# NBMC_SCHEMATIC_wout_thermistor_bridge_ex.net
KiCad netlist of a schematic drawn in EAGLE
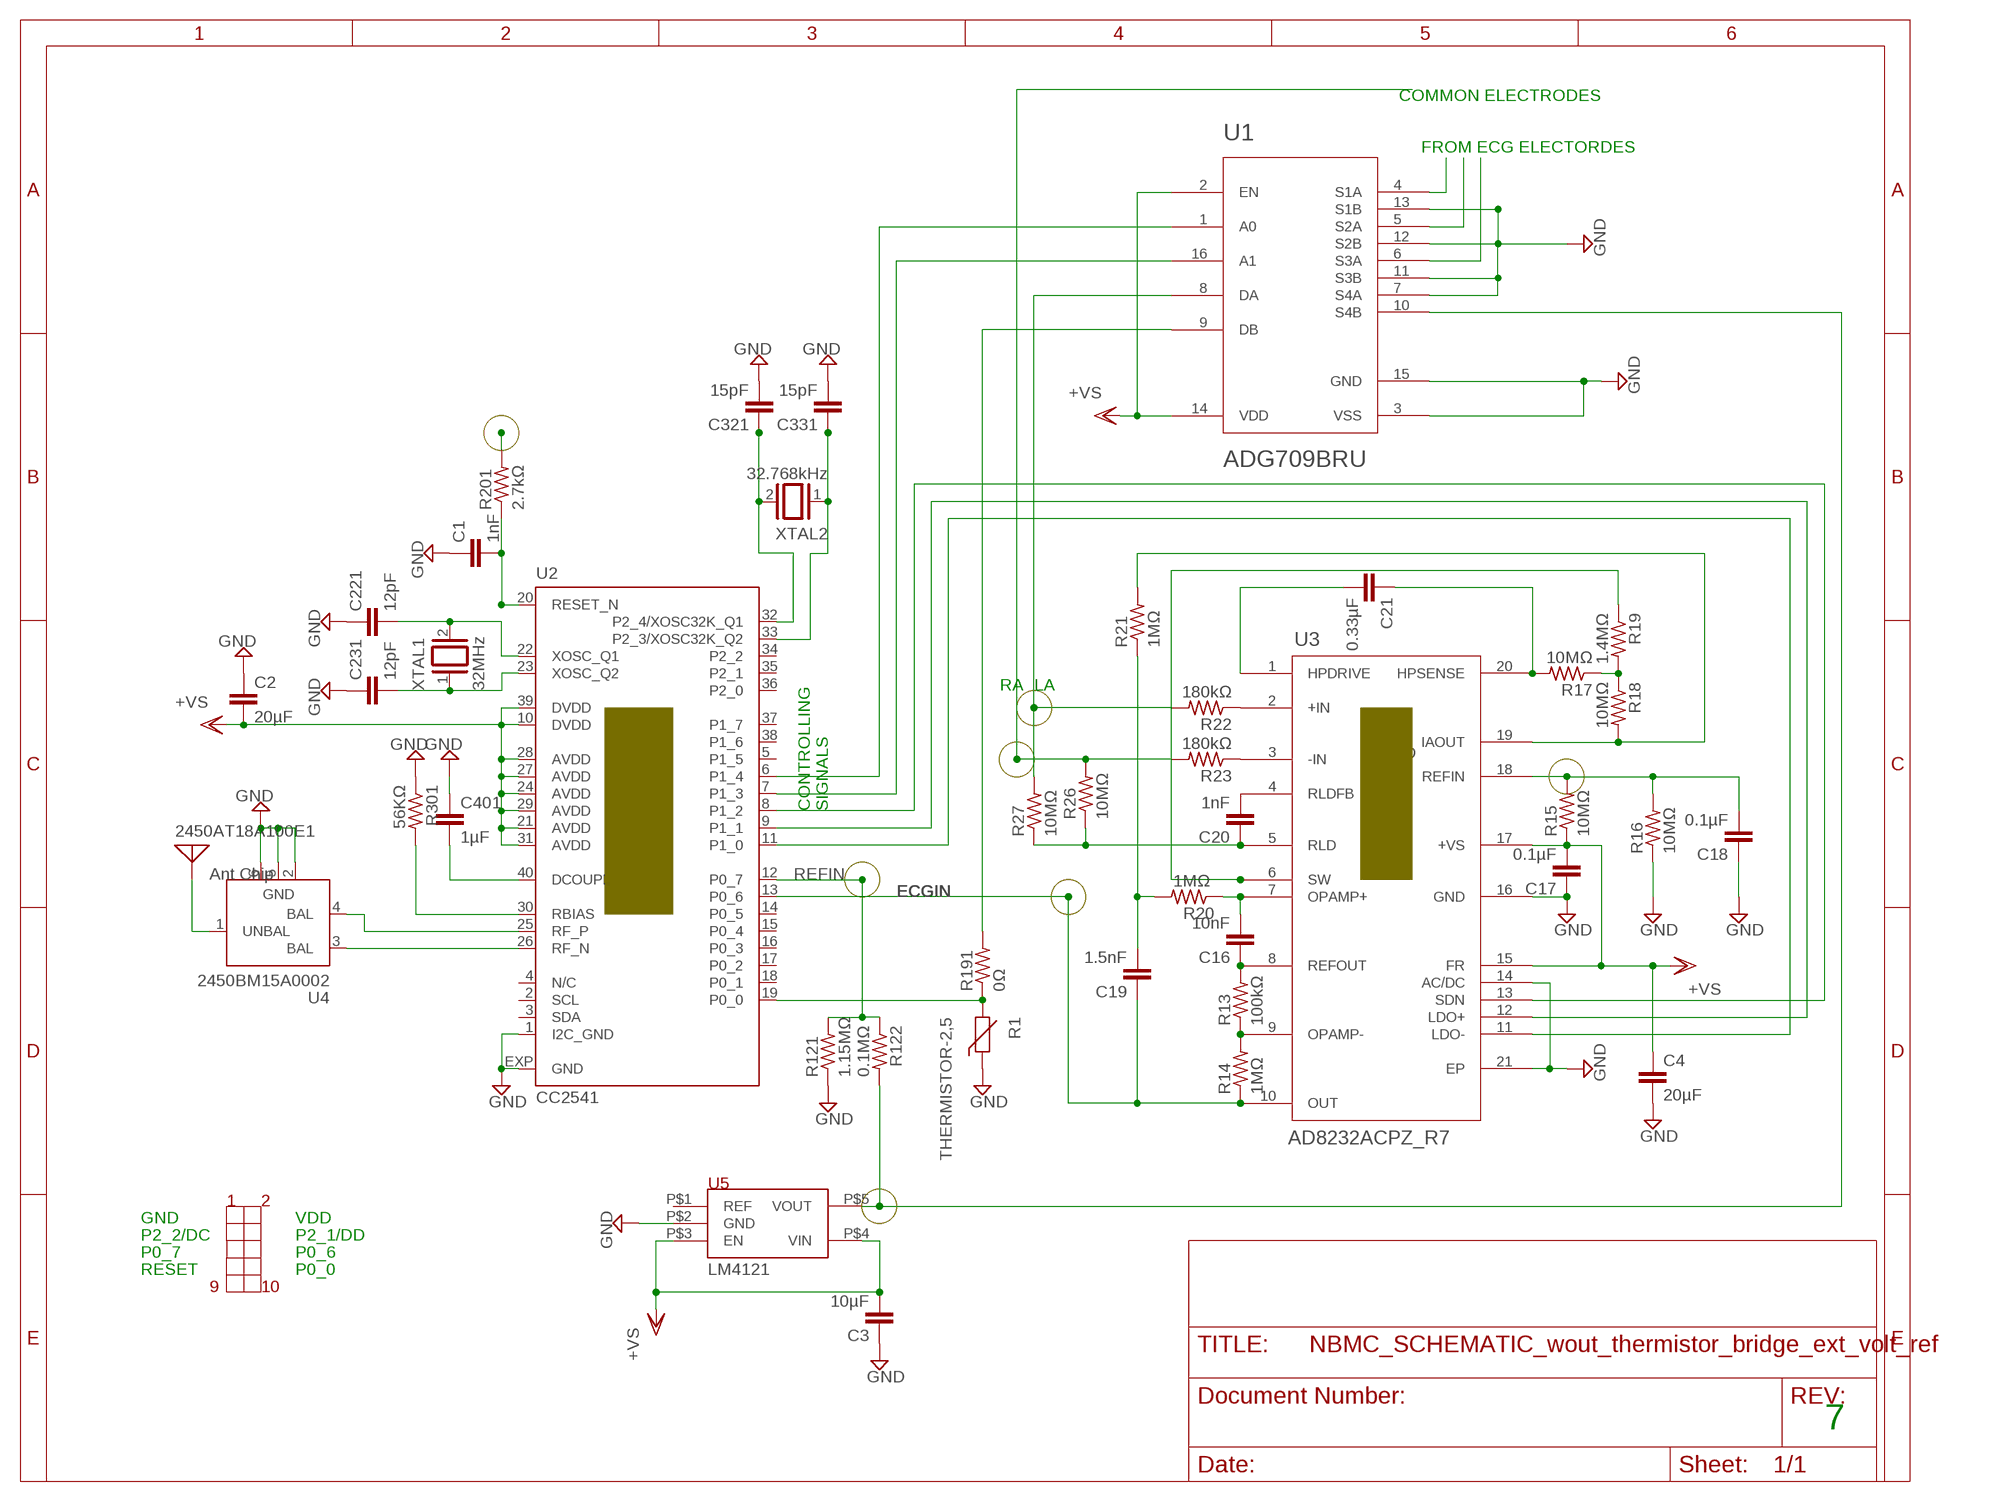
[diagram p0: schematic, sheet 1]

(export (version "E")
  (design (tool "Eeschema 10.0.6"))
  (components
    (comp (ref "2450AT18A100E1")
      (value "Ant Chip")
      (footprint "eagle-import:PAD-01")
      (libsource (lib "eagle-import") (part "ANTENNA"))
    )
    (comp (ref "C1")
      (value "1nF")
      (footprint "eagle-import:C0402")
      (libsource (lib "eagle-import") (part "C-EUC0402"))
    )
    (comp (ref "C2")
      (value "20µF")
      (footprint "eagle-import:C0402")
      (libsource (lib "eagle-import") (part "C-EUC0402"))
    )
    (comp (ref "C3")
      (value "10µF")
      (footprint "eagle-import:C0402")
      (libsource (lib "eagle-import") (part "C-EUC0402"))
    )
    (comp (ref "C4")
      (value "20µF")
      (footprint "eagle-import:C0402")
      (libsource (lib "eagle-import") (part "C-EUC0402"))
    )
    (comp (ref "C16")
      (value "10nF")
      (footprint "eagle-import:C0402")
      (libsource (lib "eagle-import") (part "C-EUC0402"))
    )
    (comp (ref "C17")
      (value "0.1µF")
      (footprint "eagle-import:C0402")
      (libsource (lib "eagle-import") (part "C-EUC0402"))
    )
    (comp (ref "C18")
      (value "0.1µF")
      (footprint "eagle-import:C0402")
      (libsource (lib "eagle-import") (part "C-EUC0402"))
    )
    (comp (ref "C19")
      (value "1.5nF")
      (footprint "eagle-import:C0402")
      (libsource (lib "eagle-import") (part "C-EUC0402"))
    )
    (comp (ref "C20")
      (value "1nF")
      (footprint "eagle-import:C0402")
      (libsource (lib "eagle-import") (part "C-EUC0402"))
    )
    (comp (ref "C21")
      (value "0.33µF")
      (footprint "eagle-import:C0402")
      (libsource (lib "eagle-import") (part "C-EUC0402"))
    )
    (comp (ref "C221")
      (value "12pF")
      (footprint "eagle-import:C0402")
      (libsource (lib "eagle-import") (part "C-EUC0402"))
    )
    (comp (ref "C231")
      (value "12pF")
      (footprint "eagle-import:C0402")
      (libsource (lib "eagle-import") (part "C-EUC0402"))
    )
    (comp (ref "C321")
      (value "15pF")
      (footprint "eagle-import:C0402")
      (libsource (lib "eagle-import") (part "C-EUC0402"))
    )
    (comp (ref "C331")
      (value "15pF")
      (footprint "eagle-import:C0402")
      (libsource (lib "eagle-import") (part "C-EUC0402"))
    )
    (comp (ref "C401")
      (value "1µF")
      (footprint "eagle-import:C0402")
      (libsource (lib "eagle-import") (part "C-EUC0402"))
    )
    (comp (ref "R1")
      (value "THERMISTOR-2,5")
      (footprint "eagle-import:RS-2,5")
      (libsource (lib "eagle-import") (part "THERMISTOR-2,5"))
    )
    (comp (ref "R13")
      (value "100kΩ")
      (footprint "eagle-import:R0402")
      (libsource (lib "eagle-import") (part "R-US_R0402"))
    )
    (comp (ref "R14")
      (value "1MΩ")
      (footprint "eagle-import:R0402")
      (libsource (lib "eagle-import") (part "R-US_R0402"))
    )
    (comp (ref "R15")
      (value "10MΩ")
      (footprint "eagle-import:R0402")
      (libsource (lib "eagle-import") (part "R-US_R0402"))
    )
    (comp (ref "R16")
      (value "10MΩ")
      (footprint "eagle-import:R0402")
      (libsource (lib "eagle-import") (part "R-US_R0402"))
    )
    (comp (ref "R17")
      (value "10MΩ")
      (footprint "eagle-import:R0402")
      (libsource (lib "eagle-import") (part "R-US_R0402"))
    )
    (comp (ref "R18")
      (value "10MΩ")
      (footprint "eagle-import:R0402")
      (libsource (lib "eagle-import") (part "R-US_R0402"))
    )
    (comp (ref "R19")
      (value "1.4MΩ")
      (footprint "eagle-import:R0402")
      (libsource (lib "eagle-import") (part "R-US_R0402"))
    )
    (comp (ref "R20")
      (value "1MΩ")
      (footprint "eagle-import:R0402")
      (libsource (lib "eagle-import") (part "R-US_R0402"))
    )
    (comp (ref "R21")
      (value "1MΩ")
      (footprint "eagle-import:R0402")
      (libsource (lib "eagle-import") (part "R-US_R0402"))
    )
    (comp (ref "R22")
      (value "180kΩ")
      (footprint "eagle-import:R0402")
      (libsource (lib "eagle-import") (part "R-US_R0402"))
    )
    (comp (ref "R23")
      (value "180kΩ")
      (footprint "eagle-import:R0402")
      (libsource (lib "eagle-import") (part "R-US_R0402"))
    )
    (comp (ref "R26")
      (value "10MΩ")
      (footprint "eagle-import:R0402")
      (libsource (lib "eagle-import") (part "R-US_R0402"))
    )
    (comp (ref "R27")
      (value "10MΩ")
      (footprint "eagle-import:R0402")
      (libsource (lib "eagle-import") (part "R-US_R0402"))
    )
    (comp (ref "R121")
      (value "1.15MΩ")
      (footprint "eagle-import:R0402")
      (libsource (lib "eagle-import") (part "R-US_R0402"))
    )
    (comp (ref "R122")
      (value "0.1MΩ")
      (footprint "eagle-import:R0402")
      (libsource (lib "eagle-import") (part "R-US_R0402"))
    )
    (comp (ref "R191")
      (value "0Ω")
      (footprint "eagle-import:R0402")
      (libsource (lib "eagle-import") (part "R-US_R0402"))
    )
    (comp (ref "R201")
      (value "2.7kΩ")
      (footprint "eagle-import:R0402")
      (libsource (lib "eagle-import") (part "R-US_R0402"))
    )
    (comp (ref "R301")
      (value "56KΩ")
      (footprint "eagle-import:R0402")
      (libsource (lib "eagle-import") (part "R-US_R0402"))
    )
    (comp (ref "U1")
      (value "ADG709BRU")
      (footprint "eagle-import:RU_16")
      (libsource (lib "eagle-import") (part "ADG709BRU"))
    )
    (comp (ref "U2")
      (value "CC2541")
      (footprint "eagle-import:RHA_S-PVQFN-N40")
      (libsource (lib "eagle-import") (part "CC2541"))
    )
    (comp (ref "U3")
      (value "AD8232ACPZ_R7")
      (footprint "eagle-import:CP_20_10")
      (libsource (lib "eagle-import") (part "AD8232ACPZ_R7"))
    )
    (comp (ref "U4")
      (value "2450BM15A0002")
      (footprint "eagle-import:2450BM15A0002")
      (libsource (lib "eagle-import") (part "2450BM15A0002"))
    )
    (comp (ref "U5")
      (value "LM4121")
      (footprint "eagle-import:0402")
      (libsource (lib "eagle-import") (part "LM4121"))
    )
    (comp (ref "XTAL1")
      (value "32MHz")
      (footprint "eagle-import:Q")
      (libsource (lib "eagle-import") (part "XTAL"))
    )
    (comp (ref "XTAL2")
      (value "32.768kHz")
      (footprint "eagle-import:Q")
      (libsource (lib "eagle-import") (part "XTAL"))
    )
  )
  (nets
    (net (code "1") (name "+VS") (class "Default")
      (node (ref "C17") (pin "2") (pinfunction "2_2") (pintype "passive"))
      (node (ref "C2") (pin "2") (pinfunction "2_2") (pintype "passive"))
      (node (ref "C3") (pin "2") (pinfunction "2_2") (pintype "passive"))
      (node (ref "C4") (pin "1") (pinfunction "1_1") (pintype "passive"))
      (node (ref "R15") (pin "1") (pinfunction "1_1") (pintype "passive"))
      (node (ref "U1") (pin "14") (pinfunction "VDD_14") (pintype "power_in"))
      (node (ref "U1") (pin "2") (pinfunction "EN_2") (pintype "passive"))
      (node (ref "U2") (pin "10") (pinfunction "DVDD_10") (pintype "power_in"))
      (node (ref "U2") (pin "21") (pinfunction "AVDD_21") (pintype "power_in"))
      (node (ref "U2") (pin "24") (pinfunction "AVDD_24") (pintype "power_in"))
      (node (ref "U2") (pin "27") (pinfunction "AVDD_27") (pintype "power_in"))
      (node (ref "U2") (pin "28") (pinfunction "AVDD_28") (pintype "power_in"))
      (node (ref "U2") (pin "29") (pinfunction "AVDD_29") (pintype "power_in"))
      (node (ref "U2") (pin "31") (pinfunction "AVDD_31") (pintype "power_in"))
      (node (ref "U2") (pin "39") (pinfunction "DVDD_39") (pintype "power_in"))
      (node (ref "U3") (pin "15") (pinfunction "FR_15") (pintype "passive"))
      (node (ref "U3") (pin "17") (pinfunction "+VS_17") (pintype "passive"))
      (node (ref "U5") (pin "P$3") (pinfunction "EN_P$3") (pintype "input"))
      (node (ref "U5") (pin "P$4") (pinfunction "VIN_P$4") (pintype "input"))
    )
    (net (code "2") (name "/ECGIN") (class "Default")
      (node (ref "C19") (pin "1") (pinfunction "1_1") (pintype "passive"))
      (node (ref "R14") (pin "1") (pinfunction "1_1") (pintype "passive"))
      (node (ref "U2") (pin "13") (pinfunction "P0_6_13") (pintype "bidirectional"))
      (node (ref "U3") (pin "10") (pinfunction "OUT_10") (pintype "passive"))
    )
    (net (code "3") (name "/N{slash}C") (class "Default")
      (node (ref "U2") (pin "4") (pinfunction "N/C_4") (pintype "power_in"))
    )
    (net (code "4") (name "/REFIN") (class "Default")
      (node (ref "R121") (pin "2") (pinfunction "2_2") (pintype "passive"))
      (node (ref "R122") (pin "1") (pinfunction "1_1") (pintype "passive"))
      (node (ref "U2") (pin "12") (pinfunction "P0_7_12") (pintype "bidirectional"))
    )
    (net (code "5") (name "GND") (class "Default")
      (node (ref "C1") (pin "1") (pinfunction "1_1") (pintype "passive"))
      (node (ref "C17") (pin "1") (pinfunction "1_1") (pintype "passive"))
      (node (ref "C18") (pin "1") (pinfunction "1_1") (pintype "passive"))
      (node (ref "C2") (pin "1") (pinfunction "1_1") (pintype "passive"))
      (node (ref "C221") (pin "1") (pinfunction "1_1") (pintype "passive"))
      (node (ref "C231") (pin "1") (pinfunction "1_1") (pintype "passive"))
      (node (ref "C3") (pin "1") (pinfunction "1_1") (pintype "passive"))
      (node (ref "C321") (pin "2") (pinfunction "2_2") (pintype "passive"))
      (node (ref "C331") (pin "2") (pinfunction "2_2") (pintype "passive"))
      (node (ref "C4") (pin "2") (pinfunction "2_2") (pintype "passive"))
      (node (ref "C401") (pin "1") (pinfunction "1_1") (pintype "passive"))
      (node (ref "R1") (pin "1") (pinfunction "1_1") (pintype "passive"))
      (node (ref "R121") (pin "1") (pinfunction "1_1") (pintype "passive"))
      (node (ref "R16") (pin "1") (pinfunction "1_1") (pintype "passive"))
      (node (ref "R301") (pin "1") (pinfunction "1_1") (pintype "passive"))
      (node (ref "U1") (pin "11") (pinfunction "S3B_11") (pintype "passive"))
      (node (ref "U1") (pin "12") (pinfunction "S2B_12") (pintype "passive"))
      (node (ref "U1") (pin "13") (pinfunction "S1B_13") (pintype "passive"))
      (node (ref "U1") (pin "15") (pinfunction "GND_15") (pintype "passive"))
      (node (ref "U1") (pin "3") (pinfunction "VSS_3") (pintype "power_in"))
      (node (ref "U1") (pin "7") (pinfunction "S4A_7") (pintype "passive"))
      (node (ref "U2") (pin "1") (pinfunction "I2C_GND_1") (pintype "power_in"))
      (node (ref "U2") (pin "EXP") (pinfunction "GND_EXP") (pintype "passive"))
      (node (ref "U3") (pin "14") (pinfunction "AC/DC_14") (pintype "passive"))
      (node (ref "U3") (pin "16") (pinfunction "GND_16") (pintype "passive"))
      (node (ref "U3") (pin "21") (pinfunction "EP_21") (pintype "passive"))
      (node (ref "U4") (pin "2") (pinfunction "GND_2") (pintype "passive"))
      (node (ref "U4") (pin "5") (pinfunction "GND_5") (pintype "passive"))
      (node (ref "U4") (pin "6") (pinfunction "GND_6") (pintype "passive"))
      (node (ref "U5") (pin "P$2") (pinfunction "GND_P$2") (pintype "bidirectional"))
    )
    (net (code "6") (name "Net-(C19-Pad2)") (class "Default")
      (node (ref "C19") (pin "2") (pinfunction "2_2") (pintype "passive"))
      (node (ref "R20") (pin "2") (pinfunction "2_2") (pintype "passive"))
      (node (ref "R21") (pin "1") (pinfunction "1_1") (pintype "passive"))
    )
    (net (code "7") (name "Net-(R17-Pad1)") (class "Default")
      (node (ref "R17") (pin "1") (pinfunction "1_1") (pintype "passive"))
      (node (ref "R18") (pin "1") (pinfunction "1_1") (pintype "passive"))
      (node (ref "R19") (pin "2") (pinfunction "2_2") (pintype "passive"))
    )
    (net (code "8") (name "Net-(R23-Pad2)") (class "Default")
      (node (ref "R23") (pin "2") (pinfunction "2_2") (pintype "passive"))
      (node (ref "R26") (pin "2") (pinfunction "2_2") (pintype "passive"))
    )
    (net (code "9") (name "Net-(U1-A0)") (class "Default")
      (node (ref "U1") (pin "1") (pinfunction "A0_1") (pintype "passive"))
      (node (ref "U2") (pin "6") (pinfunction "P1_4_6") (pintype "bidirectional"))
    )
    (net (code "10") (name "Net-(U1-A1)") (class "Default")
      (node (ref "U1") (pin "16") (pinfunction "A1_16") (pintype "passive"))
      (node (ref "U2") (pin "7") (pinfunction "P1_3_7") (pintype "bidirectional"))
    )
    (net (code "11") (name "Net-(U1-DA)") (class "Default")
      (node (ref "R22") (pin "2") (pinfunction "2_2") (pintype "passive"))
      (node (ref "R27") (pin "2") (pinfunction "2_2") (pintype "passive"))
      (node (ref "U1") (pin "8") (pinfunction "DA_8") (pintype "passive"))
    )
    (net (code "12") (name "Net-(U1-DB)") (class "Default")
      (node (ref "R191") (pin "2") (pinfunction "2_2") (pintype "passive"))
      (node (ref "U1") (pin "9") (pinfunction "DB_9") (pintype "passive"))
    )
    (net (code "13") (name "Net-(U1-S4B)") (class "Default")
      (node (ref "R122") (pin "2") (pinfunction "2_2") (pintype "passive"))
      (node (ref "U1") (pin "10") (pinfunction "S4B_10") (pintype "passive"))
      (node (ref "U5") (pin "P$5") (pinfunction "VOUT_P$5") (pintype "output"))
    )
    (net (code "14") (name "Net-(U2-DCOUPL)") (class "Default")
      (node (ref "C401") (pin "2") (pinfunction "2_2") (pintype "passive"))
      (node (ref "U2") (pin "40") (pinfunction "DCOUPL_40") (pintype "power_in"))
    )
    (net (code "15") (name "Net-(U2-P0_0)") (class "Default")
      (node (ref "R1") (pin "2") (pinfunction "2_2") (pintype "passive"))
      (node (ref "R191") (pin "1") (pinfunction "1_1") (pintype "passive"))
      (node (ref "U2") (pin "19") (pinfunction "P0_0_19") (pintype "bidirectional"))
    )
    (net (code "16") (name "Net-(U2-P1_0)") (class "Default")
      (node (ref "U2") (pin "11") (pinfunction "P1_0_11") (pintype "bidirectional"))
      (node (ref "U3") (pin "11") (pinfunction "LDO-_11") (pintype "passive"))
    )
    (net (code "17") (name "Net-(U2-P1_1)") (class "Default")
      (node (ref "U2") (pin "9") (pinfunction "P1_1_9") (pintype "bidirectional"))
      (node (ref "U3") (pin "12") (pinfunction "LDO+_12") (pintype "passive"))
    )
    (net (code "18") (name "Net-(U2-P1_2)") (class "Default")
      (node (ref "U2") (pin "8") (pinfunction "P1_2_8") (pintype "bidirectional"))
      (node (ref "U3") (pin "13") (pinfunction "SDN_13") (pintype "passive"))
    )
    (net (code "19") (name "Net-(U2-P2_3{slash}XOSC32K_Q2)") (class "Default")
      (node (ref "C331") (pin "1") (pinfunction "1_1") (pintype "passive"))
      (node (ref "U2") (pin "33") (pinfunction "P2_3/XOSC32K_Q2_33") (pintype "bidirectional"))
      (node (ref "XTAL2") (pin "1") (pinfunction "1_1") (pintype "passive"))
    )
    (net (code "20") (name "Net-(U2-P2_4{slash}XOSC32K_Q1)") (class "Default")
      (node (ref "C321") (pin "1") (pinfunction "1_1") (pintype "passive"))
      (node (ref "U2") (pin "32") (pinfunction "P2_4/XOSC32K_Q1_32") (pintype "bidirectional"))
      (node (ref "XTAL2") (pin "2") (pinfunction "2_2") (pintype "passive"))
    )
    (net (code "21") (name "Net-(U2-RBIAS)") (class "Default")
      (node (ref "R301") (pin "2") (pinfunction "2_2") (pintype "passive"))
      (node (ref "U2") (pin "30") (pinfunction "RBIAS_30") (pintype "bidirectional"))
    )
    (net (code "22") (name "Net-(U2-RESET_N)") (class "Default")
      (node (ref "C1") (pin "2") (pinfunction "2_2") (pintype "passive"))
      (node (ref "R201") (pin "1") (pinfunction "1_1") (pintype "passive"))
      (node (ref "U2") (pin "20") (pinfunction "RESET_N_20") (pintype "input"))
    )
    (net (code "23") (name "Net-(U2-RF_N)") (class "Default")
      (node (ref "U2") (pin "26") (pinfunction "RF_N_26") (pintype "bidirectional"))
      (node (ref "U4") (pin "3") (pinfunction "BAL_3") (pintype "passive"))
    )
    (net (code "24") (name "Net-(U2-RF_P)") (class "Default")
      (node (ref "U2") (pin "25") (pinfunction "RF_P_25") (pintype "bidirectional"))
      (node (ref "U4") (pin "4") (pinfunction "BAL_4") (pintype "passive"))
    )
    (net (code "25") (name "Net-(U2-XOSC_Q1)") (class "Default")
      (node (ref "C221") (pin "2") (pinfunction "2_2") (pintype "passive"))
      (node (ref "U2") (pin "22") (pinfunction "XOSC_Q1_22") (pintype "bidirectional"))
      (node (ref "XTAL1") (pin "2") (pinfunction "2_2") (pintype "passive"))
    )
    (net (code "26") (name "Net-(U2-XOSC_Q2)") (class "Default")
      (node (ref "C231") (pin "2") (pinfunction "2_2") (pintype "passive"))
      (node (ref "U2") (pin "23") (pinfunction "XOSC_Q2_23") (pintype "bidirectional"))
      (node (ref "XTAL1") (pin "1") (pinfunction "1_1") (pintype "passive"))
    )
    (net (code "27") (name "Net-(U3-+IN)") (class "Default")
      (node (ref "R22") (pin "1") (pinfunction "1_1") (pintype "passive"))
      (node (ref "U3") (pin "2") (pinfunction "+IN_2") (pintype "passive"))
    )
    (net (code "28") (name "Net-(U3--IN)") (class "Default")
      (node (ref "R23") (pin "1") (pinfunction "1_1") (pintype "passive"))
      (node (ref "U3") (pin "3") (pinfunction "-IN_3") (pintype "passive"))
    )
    (net (code "29") (name "Net-(U3-HPDRIVE)") (class "Default")
      (node (ref "C21") (pin "2") (pinfunction "2_2") (pintype "passive"))
      (node (ref "U3") (pin "1") (pinfunction "HPDRIVE_1") (pintype "passive"))
    )
    (net (code "30") (name "Net-(U3-HPSENSE)") (class "Default")
      (node (ref "C21") (pin "1") (pinfunction "1_1") (pintype "passive"))
      (node (ref "R17") (pin "2") (pinfunction "2_2") (pintype "passive"))
      (node (ref "U3") (pin "20") (pinfunction "HPSENSE_20") (pintype "passive"))
    )
    (net (code "31") (name "Net-(U3-IAOUT)") (class "Default")
      (node (ref "R18") (pin "2") (pinfunction "2_2") (pintype "passive"))
      (node (ref "R21") (pin "2") (pinfunction "2_2") (pintype "passive"))
      (node (ref "U3") (pin "19") (pinfunction "IAOUT_19") (pintype "passive"))
    )
    (net (code "32") (name "Net-(U3-OPAMP+)") (class "Default")
      (node (ref "C16") (pin "2") (pinfunction "2_2") (pintype "passive"))
      (node (ref "R20") (pin "1") (pinfunction "1_1") (pintype "passive"))
      (node (ref "U3") (pin "7") (pinfunction "OPAMP+_7") (pintype "passive"))
    )
    (net (code "33") (name "Net-(U3-OPAMP-)") (class "Default")
      (node (ref "R13") (pin "1") (pinfunction "1_1") (pintype "passive"))
      (node (ref "R14") (pin "2") (pinfunction "2_2") (pintype "passive"))
      (node (ref "U3") (pin "9") (pinfunction "OPAMP-_9") (pintype "passive"))
    )
    (net (code "34") (name "Net-(U3-REFIN)") (class "Default")
      (node (ref "C18") (pin "2") (pinfunction "2_2") (pintype "passive"))
      (node (ref "R15") (pin "2") (pinfunction "2_2") (pintype "passive"))
      (node (ref "R16") (pin "2") (pinfunction "2_2") (pintype "passive"))
      (node (ref "U3") (pin "18") (pinfunction "REFIN_18") (pintype "passive"))
    )
    (net (code "35") (name "Net-(U3-REFOUT)") (class "Default")
      (node (ref "C16") (pin "1") (pinfunction "1_1") (pintype "passive"))
      (node (ref "R13") (pin "2") (pinfunction "2_2") (pintype "passive"))
      (node (ref "U3") (pin "8") (pinfunction "REFOUT_8") (pintype "passive"))
    )
    (net (code "36") (name "Net-(U3-RLD)") (class "Default")
      (node (ref "C20") (pin "1") (pinfunction "1_1") (pintype "passive"))
      (node (ref "R26") (pin "1") (pinfunction "1_1") (pintype "passive"))
      (node (ref "R27") (pin "1") (pinfunction "1_1") (pintype "passive"))
      (node (ref "U3") (pin "5") (pinfunction "RLD_5") (pintype "passive"))
    )
    (net (code "37") (name "Net-(U3-RLDFB)") (class "Default")
      (node (ref "C20") (pin "2") (pinfunction "2_2") (pintype "passive"))
      (node (ref "U3") (pin "4") (pinfunction "RLDFB_4") (pintype "passive"))
    )
    (net (code "38") (name "Net-(U3-SW)") (class "Default")
      (node (ref "R19") (pin "1") (pinfunction "1_1") (pintype "passive"))
      (node (ref "U3") (pin "6") (pinfunction "SW_6") (pintype "passive"))
    )
    (net (code "39") (name "Net-(U4-UNBAL)") (class "Default")
      (node (ref "2450AT18A100E1") (pin "1") (pinfunction "1_1") (pintype "output"))
      (node (ref "U4") (pin "1") (pinfunction "UNBAL_1") (pintype "passive"))
    )
    (net (code "40") (name "unconnected-(R201-Pad2)") (class "Default")
      (node (ref "R201") (pin "2") (pinfunction "2_2") (pintype "passive"))
    )
    (net (code "41") (name "unconnected-(U1-S1A-Pad4)") (class "Default")
      (node (ref "U1") (pin "4") (pinfunction "S1A_4") (pintype "passive"))
    )
    (net (code "42") (name "unconnected-(U1-S2A-Pad5)") (class "Default")
      (node (ref "U1") (pin "5") (pinfunction "S2A_5") (pintype "passive"))
    )
    (net (code "43") (name "unconnected-(U1-S3A-Pad6)") (class "Default")
      (node (ref "U1") (pin "6") (pinfunction "S3A_6") (pintype "passive"))
    )
    (net (code "44") (name "unconnected-(U2-P0_1-Pad18)") (class "Default")
      (node (ref "U2") (pin "18") (pinfunction "P0_1_18") (pintype "bidirectional"))
    )
    (net (code "45") (name "unconnected-(U2-P0_2-Pad17)") (class "Default")
      (node (ref "U2") (pin "17") (pinfunction "P0_2_17") (pintype "bidirectional"))
    )
    (net (code "46") (name "unconnected-(U2-P0_3-Pad16)") (class "Default")
      (node (ref "U2") (pin "16") (pinfunction "P0_3_16") (pintype "bidirectional"))
    )
    (net (code "47") (name "unconnected-(U2-P0_4-Pad15)") (class "Default")
      (node (ref "U2") (pin "15") (pinfunction "P0_4_15") (pintype "bidirectional"))
    )
    (net (code "48") (name "unconnected-(U2-P0_5-Pad14)") (class "Default")
      (node (ref "U2") (pin "14") (pinfunction "P0_5_14") (pintype "bidirectional"))
    )
    (net (code "49") (name "unconnected-(U2-P1_5-Pad5)") (class "Default")
      (node (ref "U2") (pin "5") (pinfunction "P1_5_5") (pintype "bidirectional"))
    )
    (net (code "50") (name "unconnected-(U2-P1_6-Pad38)") (class "Default")
      (node (ref "U2") (pin "38") (pinfunction "P1_6_38") (pintype "bidirectional"))
    )
    (net (code "51") (name "unconnected-(U2-P1_7-Pad37)") (class "Default")
      (node (ref "U2") (pin "37") (pinfunction "P1_7_37") (pintype "bidirectional"))
    )
    (net (code "52") (name "unconnected-(U2-P2_0-Pad36)") (class "Default")
      (node (ref "U2") (pin "36") (pinfunction "P2_0_36") (pintype "bidirectional"))
    )
    (net (code "53") (name "unconnected-(U2-P2_1-Pad35)") (class "Default")
      (node (ref "U2") (pin "35") (pinfunction "P2_1_35") (pintype "bidirectional"))
    )
    (net (code "54") (name "unconnected-(U2-P2_2-Pad34)") (class "Default")
      (node (ref "U2") (pin "34") (pinfunction "P2_2_34") (pintype "bidirectional"))
    )
    (net (code "55") (name "unconnected-(U2-SCL-Pad2)") (class "Default")
      (node (ref "U2") (pin "2") (pinfunction "SCL_2") (pintype "bidirectional"))
    )
    (net (code "56") (name "unconnected-(U2-SDA-Pad3)") (class "Default")
      (node (ref "U2") (pin "3") (pinfunction "SDA_3") (pintype "bidirectional"))
    )
    (net (code "57") (name "unconnected-(U5-REF-PadP$1)") (class "Default")
      (node (ref "U5") (pin "P$1") (pinfunction "REF_P$1") (pintype "bidirectional"))
    )
  )
)
